# v12.net
KiCad netlist of a schematic drawn in Altium Designer
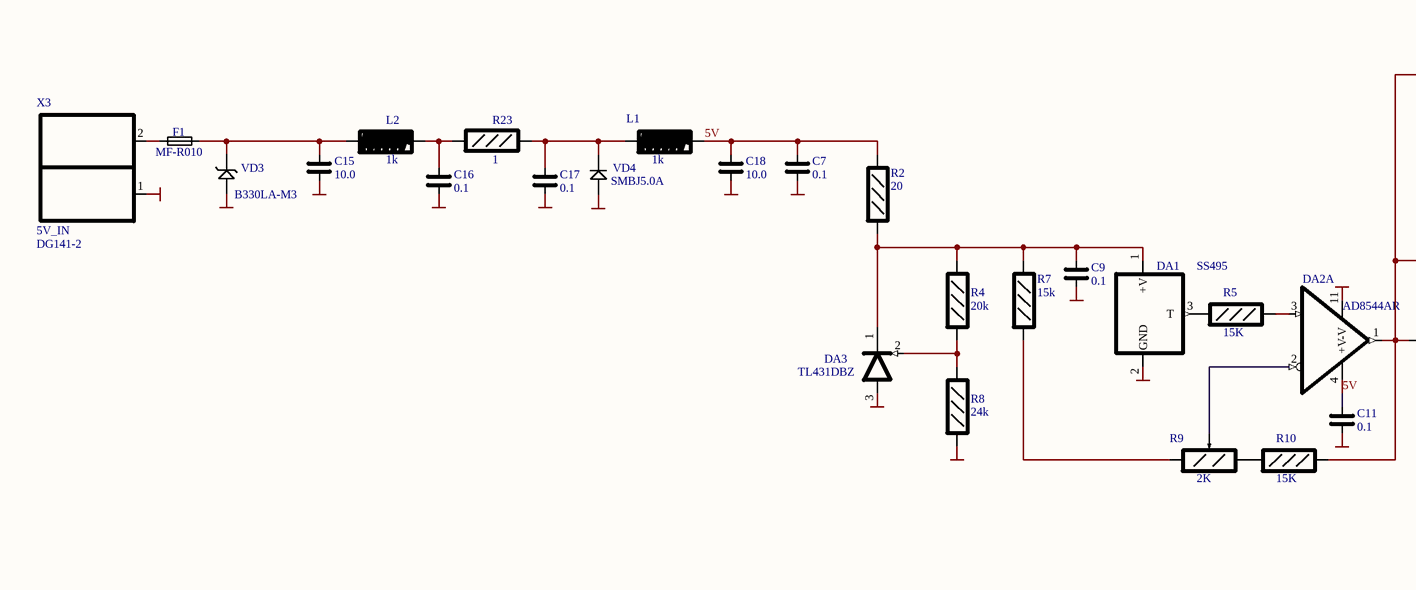
[diagram p0: v12.SchDoc, left]
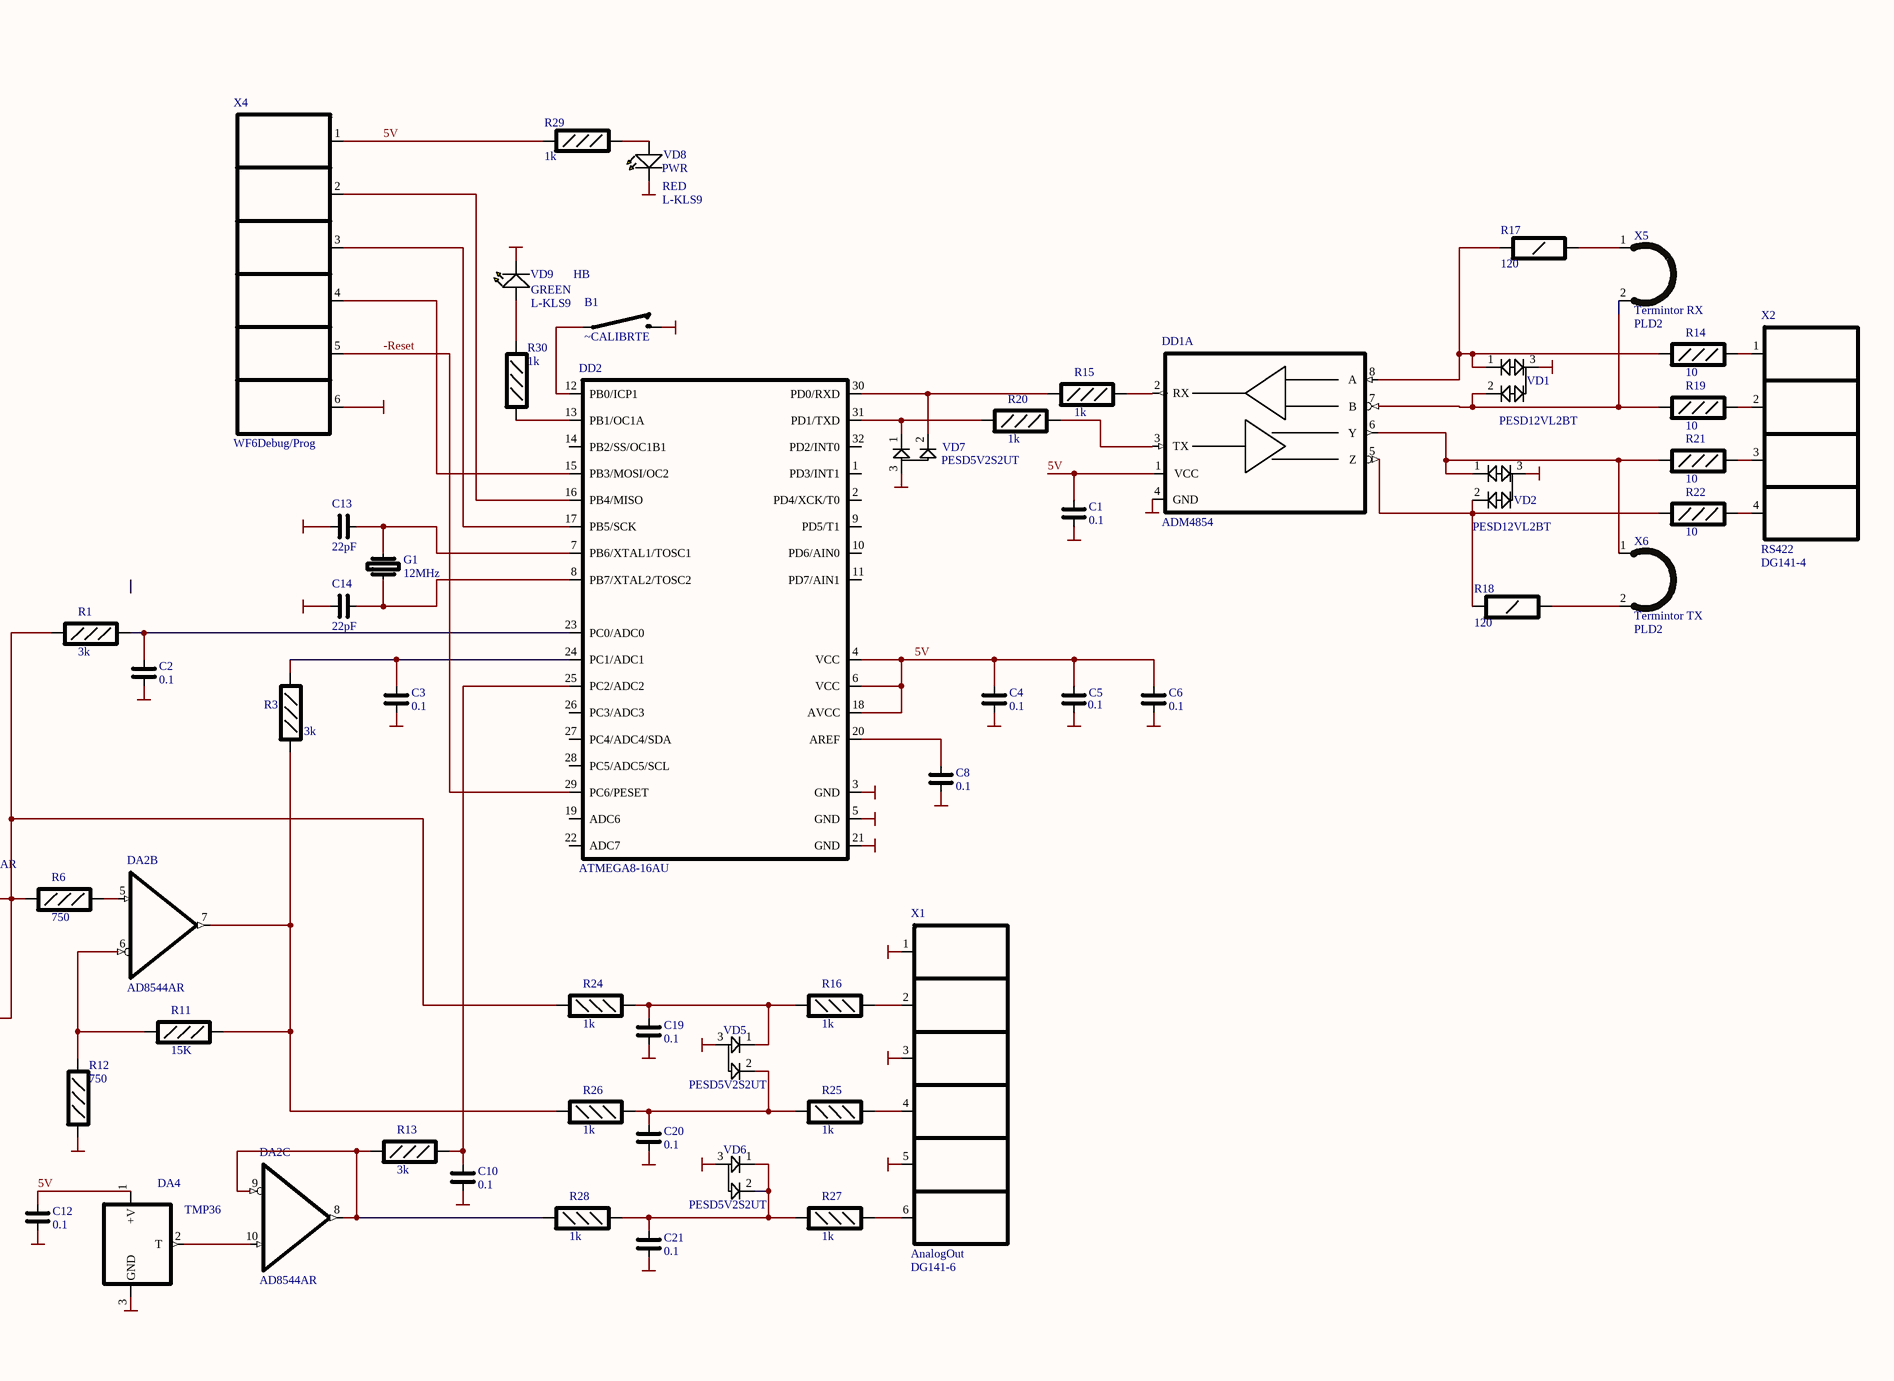
[diagram p1: v12.SchDoc, right]

(export (version "E")
  (design (tool "Eeschema 10.0.6"))
  (components
    (comp (ref "B1")
      (value "~CALIBRTE")
      (footprint "DIP_4-450_PB_OMRON_B3F-1070")
      (description "Push button wo latch")
      (libsource (lib "L1") (part "PushBt"))
    )
    (comp (ref "C1")
      (value "0.1")
      (footprint "CAPC1608X85N")
      (description "Chip capasitor 0603")
      (libsource (lib "L1") (part "CAP00603"))
    )
    (comp (ref "C2")
      (value "0.1")
      (footprint "CAPC1608X85N")
      (description "Chip capasitor 0603")
      (libsource (lib "L1") (part "CAP00603"))
    )
    (comp (ref "C3")
      (value "0.1")
      (footprint "CAPC1608X85N")
      (description "Chip capasitor 0603")
      (libsource (lib "L1") (part "CAP00603"))
    )
    (comp (ref "C4")
      (value "0.1")
      (footprint "CAPC1608X85N")
      (description "Chip capasitor 0603")
      (libsource (lib "L1") (part "CAP00603"))
    )
    (comp (ref "C5")
      (value "0.1")
      (footprint "CAPC1608X85N")
      (description "Chip capasitor 0603")
      (libsource (lib "L1") (part "CAP00603"))
    )
    (comp (ref "C6")
      (value "0.1")
      (footprint "CAPC1608X85N")
      (description "Chip capasitor 0603")
      (libsource (lib "L1") (part "CAP00603"))
    )
    (comp (ref "C7")
      (value "0.1")
      (footprint "CAPC1608X85N")
      (description "Chip capasitor 0603")
      (libsource (lib "L1") (part "CAP00603"))
    )
    (comp (ref "C8")
      (value "0.1")
      (footprint "CAPC1608X85N")
      (description "Chip capasitor 0603")
      (libsource (lib "L1") (part "CAP00603"))
    )
    (comp (ref "C9")
      (value "0.1")
      (footprint "CAPC1608X85N")
      (description "Chip capasitor 0603")
      (libsource (lib "L1") (part "CAP00603"))
    )
    (comp (ref "C10")
      (value "0.1")
      (footprint "CAPC1608X85N")
      (description "Chip capasitor 0603")
      (libsource (lib "L1") (part "CAP00603"))
    )
    (comp (ref "C11")
      (value "0.1")
      (footprint "CAPC1608X85N")
      (description "Chip capasitor 0603")
      (libsource (lib "L1") (part "CAP00603"))
    )
    (comp (ref "C12")
      (value "0.1")
      (footprint "CAPC1608X85N")
      (description "Chip capasitor 0603")
      (libsource (lib "L1") (part "CAP00603"))
    )
    (comp (ref "C13")
      (value "22pF")
      (footprint "CAPC1608X85N")
      (description "Chip capasitor 0603")
      (libsource (lib "L1") (part "CAP00603"))
    )
    (comp (ref "C14")
      (value "22pF")
      (footprint "CAPC1608X85N")
      (description "Chip capasitor 0603")
      (libsource (lib "L1") (part "CAP00603"))
    )
    (comp (ref "C15")
      (value "10.0")
      (footprint "CAPC3216X152N")
      (description "Chip capasitor 1206")
      (libsource (lib "L1") (part "CAP1206"))
    )
    (comp (ref "C16")
      (value "0.1")
      (footprint "CAPC1608X85N")
      (description "Chip capasitor 0603")
      (libsource (lib "L1") (part "CAP00603"))
    )
    (comp (ref "C17")
      (value "0.1")
      (footprint "CAPC1608X85N")
      (description "Chip capasitor 0603")
      (libsource (lib "L1") (part "CAP00603"))
    )
    (comp (ref "C18")
      (value "10.0")
      (footprint "CAPC3216X152N")
      (description "Chip capasitor 1206")
      (libsource (lib "L1") (part "CAP1206"))
    )
    (comp (ref "C19")
      (value "0.1")
      (footprint "CAPC1608X85N")
      (description "Chip capasitor 0603")
      (libsource (lib "L1") (part "CAP00603"))
    )
    (comp (ref "C20")
      (value "0.1")
      (footprint "CAPC1608X85N")
      (description "Chip capasitor 0603")
      (libsource (lib "L1") (part "CAP00603"))
    )
    (comp (ref "C21")
      (value "0.1")
      (footprint "CAPC1608X85N")
      (description "Chip capasitor 0603")
      (libsource (lib "L1") (part "CAP00603"))
    )
    (comp (ref "DA1")
      (value "SS495")
      (footprint "TO92H_3-127L - spec1")
      (description "10mV / C Temperature sensor")
      (libsource (lib "L1") (part "SS495"))
    )
    (comp (ref "DA2")
      (value "AD8544AR")
      (footprint "SOIC_14-127")
      (description "Quad rail to rail i&O OpAmp. 2V7-5V 5 Single power supply. MOSFET in. SOIC14 Package")
      (libsource (lib "L1") (part "AD8544AR"))
    )
    (comp (ref "DA3")
      (value "TL431DBZ")
      (footprint "SOT23-95")
      (description "Adjustable voltage reference")
      (libsource (lib "L1") (part "TL431DBZ"))
    )
    (comp (ref "DA4")
      (value "TMP36")
      (footprint "TO-92AA-P127")
      (description "10mV / C Temperature sensor")
      (libsource (lib "L1") (part "TMP36v"))
    )
    (comp (ref "DD1")
      (value "ADM4854")
      (footprint "SOIC8")
      (description "Full Duplex RS-422 Transceivers")
      (libsource (lib "L1") (part "ADM4854"))
    )
    (comp (ref "DD2")
      (value "ATMEGA8-16AU")
      (footprint "TQFP_32-80")
      (description "8bit uController")
      (libsource (lib "L1") (part "ATMEGA8-16AU"))
    )
    (comp (ref "F1")
      (value "MF-R010")
      (footprint "MF-R-508")
      (description "Fuse")
      (libsource (lib "L1") (part "MF-R-0"))
    )
    (comp (ref "G1")
      (value "12MHz")
      (footprint "XTAL_HC-49/U")
      (description "Quartz resonator")
      (libsource (lib "L1") (part "HC49U"))
    )
    (comp (ref "L1")
      (value "1k")
      (footprint "RESC2012X50N")
      (description "SMD Ferrite bead 0805")
      (libsource (lib "L1") (part "BLM21"))
    )
    (comp (ref "L2")
      (value "1k")
      (footprint "RESC2012X50N")
      (description "SMD Ferrite bead 0805")
      (libsource (lib "L1") (part "BLM21"))
    )
    (comp (ref "R1")
      (value "3k")
      (footprint "RESC1608X50N")
      (description "Chip resistor 0603")
      (libsource (lib "") (part "Res0603_2"))
    )
    (comp (ref "R2")
      (value "20")
      (footprint "RESC1608X50N")
      (description "Chip resistor 0603")
      (libsource (lib "") (part "Res0603_1"))
    )
    (comp (ref "R3")
      (value "3k")
      (footprint "RESC1608X50N")
      (description "Chip resistor 0603")
      (libsource (lib "") (part "Res0603_1"))
    )
    (comp (ref "R4")
      (value "20k")
      (footprint "RESC1608X50N")
      (description "Chip resistor 0603")
      (libsource (lib "") (part "Res0603_1"))
    )
    (comp (ref "R5")
      (value "15K")
      (footprint "RESC1608X50N")
      (description "Chip resistor 0603")
      (libsource (lib "") (part "Res0603_2"))
    )
    (comp (ref "R6")
      (value "750")
      (footprint "RESC1608X50N")
      (description "Chip resistor 0603")
      (libsource (lib "") (part "Res0603_2"))
    )
    (comp (ref "R7")
      (value "15k")
      (footprint "RESC1608X50N")
      (description "Chip resistor 0603")
      (libsource (lib "") (part "Res0603_1"))
    )
    (comp (ref "R8")
      (value "24k")
      (footprint "RESC1608X50N")
      (description "Chip resistor 0603")
      (libsource (lib "") (part "Res0603_1"))
    )
    (comp (ref "R9")
      (value "2K")
      (footprint "TRIM_BOURNS_3296Y")
      (description "Trimm Resistor")
      (libsource (lib "L1") (part "3296"))
    )
    (comp (ref "R10")
      (value "15K")
      (footprint "RESC1608X50N")
      (description "Chip resistor 0603")
      (libsource (lib "") (part "Res0603_2"))
    )
    (comp (ref "R11")
      (value "15K")
      (footprint "RESC1608X50N")
      (description "Chip resistor 0603")
      (libsource (lib "") (part "Res0603_2"))
    )
    (comp (ref "R12")
      (value "750")
      (footprint "RESC1608X50N")
      (description "Chip resistor 0603")
      (libsource (lib "") (part "Res0603_1"))
    )
    (comp (ref "R13")
      (value "3k")
      (footprint "RESC1608X50N")
      (description "Chip resistor 0603")
      (libsource (lib "") (part "Res0603_2"))
    )
    (comp (ref "R14")
      (value "10")
      (footprint "RESC1608X50N")
      (description "Chip resistor 0603")
      (libsource (lib "") (part "Res0603_2"))
    )
    (comp (ref "R15")
      (value "1k")
      (footprint "RESC1608X50N")
      (description "Chip resistor 0603")
      (libsource (lib "") (part "Res0603_2"))
    )
    (comp (ref "R16")
      (value "1k")
      (footprint "RESC1608X50N")
      (description "Chip resistor 0603")
      (libsource (lib "L1") (part "Res0603"))
    )
    (comp (ref "R17")
      (value "120")
      (footprint "RESC3216X65N")
      (description "Chip resistor 1206")
      (libsource (lib "L1") (part "Res1206"))
    )
    (comp (ref "R18")
      (value "120")
      (footprint "RESC3216X65N")
      (description "Chip resistor 1206")
      (libsource (lib "L1") (part "Res1206"))
    )
    (comp (ref "R19")
      (value "10")
      (footprint "RESC1608X50N")
      (description "Chip resistor 0603")
      (libsource (lib "") (part "Res0603_2"))
    )
    (comp (ref "R20")
      (value "1k")
      (footprint "RESC1608X50N")
      (description "Chip resistor 0603")
      (libsource (lib "") (part "Res0603_2"))
    )
    (comp (ref "R21")
      (value "10")
      (footprint "RESC1608X50N")
      (description "Chip resistor 0603")
      (libsource (lib "") (part "Res0603_2"))
    )
    (comp (ref "R22")
      (value "10")
      (footprint "RESC1608X50N")
      (description "Chip resistor 0603")
      (libsource (lib "") (part "Res0603_2"))
    )
    (comp (ref "R23")
      (value "1")
      (footprint "RESC1608X50N")
      (description "Chip resistor 0603")
      (libsource (lib "") (part "Res0603_3"))
    )
    (comp (ref "R24")
      (value "1k")
      (footprint "RESC1608X50N")
      (description "Chip resistor 0603")
      (libsource (lib "L1") (part "Res0603"))
    )
    (comp (ref "R25")
      (value "1k")
      (footprint "RESC1608X50N")
      (description "Chip resistor 0603")
      (libsource (lib "L1") (part "Res0603"))
    )
    (comp (ref "R26")
      (value "1k")
      (footprint "RESC1608X50N")
      (description "Chip resistor 0603")
      (libsource (lib "L1") (part "Res0603"))
    )
    (comp (ref "R27")
      (value "1k")
      (footprint "RESC1608X50N")
      (description "Chip resistor 0603")
      (libsource (lib "L1") (part "Res0603"))
    )
    (comp (ref "R28")
      (value "1k")
      (footprint "RESC1608X50N")
      (description "Chip resistor 0603")
      (libsource (lib "L1") (part "Res0603"))
    )
    (comp (ref "R29")
      (value "1k")
      (footprint "RESC1608X50N")
      (description "Chip resistor 0603")
      (libsource (lib "") (part "Res0603_3"))
    )
    (comp (ref "R30")
      (value "1k")
      (footprint "RESC1608X50N")
      (description "Chip resistor 0603")
      (libsource (lib "") (part "Res0603_1"))
    )
    (comp (ref "VD1")
      (value "PESD12VL2BT")
      (footprint "SO23-95")
      (description "Low capacitance double bidirectional ESD protection diodes in SOT23")
      (libsource (lib "L1") (part "PESDxxL2BT"))
    )
    (comp (ref "VD2")
      (value "PESD12VL2BT")
      (footprint "SO23-95")
      (description "Low capacitance double bidirectional ESD protection diodes in SOT23")
      (libsource (lib "L1") (part "PESDxxL2BT"))
    )
    (comp (ref "VD3")
      (value "B330LA-M3")
      (footprint "DO214")
      (description "3A 40V Schottky Diode")
      (libsource (lib "L1") (part "B330LA-M3"))
    )
    (comp (ref "VD4")
      (value "SMBJ5.0A")
      (footprint "DO214")
      (description "TVS surface mount diode")
      (libsource (lib "L1") (part "SMBJxxA"))
    )
    (comp (ref "VD5")
      (value "PESD5V2S2UT")
      (footprint "SO23-95")
      (description "Low capacitance double  ESD protection diodes in SOT23")
      (libsource (lib "L1") (part "PESDxxS2UT"))
    )
    (comp (ref "VD6")
      (value "PESD5V2S2UT")
      (footprint "SO23-95")
      (description "Low capacitance double  ESD protection diodes in SOT23")
      (libsource (lib "L1") (part "PESDxxS2UT"))
    )
    (comp (ref "VD7")
      (value "PESD5V2S2UT")
      (footprint "SO23-95")
      (description "Low capacitance double  ESD protection diodes in SOT23")
      (libsource (lib "L1") (part "PESDxxS2UT"))
    )
    (comp (ref "VD8")
      (value "PWR")
      (footprint "LED0603")
      (description "Chip LED SMD 0603")
      (fields (field (name "COLOR") "RED") (field (name "DEVICE") "L-KLS9"))
      (libsource (lib "L1") (part "L-KLS9-T0603"))
    )
    (comp (ref "VD9")
      (value "HB")
      (footprint "LED0603")
      (description "Chip LED SMD 0603")
      (fields (field (name "COLOR") "GREEN") (field (name "DEVICE") "L-KLS9"))
      (libsource (lib "L1") (part "L-KLS9-T0603"))
    )
    (comp (ref "X1")
      (value "AnalogOut")
      (footprint "DIP_CLEMM_6-254_F")
      (description "6 pin terminal spring clamp 2.54mm pitch")
      (fields (field (name "DEVICE") "DG141-6"))
      (libsource (lib "L1") (part "DG141-6"))
    )
    (comp (ref "X2")
      (value "RS422")
      (footprint "DIP_CLEMM_4-254_F")
      (description "4 pin terminal spring clamp 2.54mm pitch")
      (fields (field (name "DEVICE") "DG141-4"))
      (libsource (lib "L1") (part "DG141-4"))
    )
    (comp (ref "X3")
      (value "5V_IN")
      (footprint "DIP_CLEMM_2-254_F")
      (description "2 pin terminal spring clamp 2.54mm pitch")
      (fields (field (name "DEVICE") "DG141-2"))
      (libsource (lib "L1") (part "DG141-2"))
    )
    (comp (ref "X4")
      (value "WF6Debug/Prog")
      (footprint "SIP_6-254")
      (description "6 pin TRH connector 2.54mm pitch")
      (libsource (lib "L1") (part "WF6"))
    )
    (comp (ref "X5")
      (value "Termintor RX")
      (footprint "DIP_2-254_WO_CASE")
      (description "2 pin TRH connector 2.54mm pitch")
      (fields (field (name "DEVICE") "PLD2"))
      (libsource (lib "L1") (part "PLD2"))
    )
    (comp (ref "X6")
      (value "Termintor TX")
      (footprint "DIP_2-254_WO_CASE")
      (description "2 pin TRH connector 2.54mm pitch")
      (fields (field (name "DEVICE") "PLD2"))
      (libsource (lib "L1") (part "PLD2"))
    )
  )
  (nets
    (net (code "1") (name "/-Reset") (class "Default")
      (node (ref "DD2") (pin "29") (pinfunction "PC6/PESET_29") (pintype "passive"))
      (node (ref "X4") (pin "5") (pinfunction "5_5") (pintype "passive"))
    )
    (net (code "2") (name "/5V") (class "Default")
      (node (ref "C1") (pin "2") (pinfunction "2_2") (pintype "passive"))
      (node (ref "C11") (pin "2") (pinfunction "2_2") (pintype "passive"))
      (node (ref "C12") (pin "2") (pinfunction "2_2") (pintype "passive"))
      (node (ref "C18") (pin "2") (pinfunction "2_2") (pintype "passive"))
      (node (ref "C4") (pin "2") (pinfunction "2_2") (pintype "passive"))
      (node (ref "C5") (pin "2") (pinfunction "2_2") (pintype "passive"))
      (node (ref "C6") (pin "2") (pinfunction "2_2") (pintype "passive"))
      (node (ref "C7") (pin "2") (pinfunction "2_2") (pintype "passive"))
      (node (ref "DA2") (pin "4") (pinfunction "+V_4") (pintype "power_in"))
      (node (ref "DA4") (pin "1") (pinfunction "+V_1") (pintype "power_in"))
      (node (ref "DD1") (pin "1") (pinfunction "VCC_1") (pintype "power_in"))
      (node (ref "DD2") (pin "18") (pinfunction "AVCC_18") (pintype "passive"))
      (node (ref "DD2") (pin "4") (pinfunction "VCC_4") (pintype "passive"))
      (node (ref "DD2") (pin "6") (pinfunction "VCC_6") (pintype "passive"))
      (node (ref "L1") (pin "2") (pinfunction "2_2") (pintype "passive"))
      (node (ref "R2") (pin "2") (pinfunction "2_2") (pintype "passive"))
      (node (ref "R29") (pin "2") (pinfunction "2_2") (pintype "passive"))
      (node (ref "X4") (pin "1") (pinfunction "1_1") (pintype "passive"))
    )
    (net (code "3") (name "GND") (class "Default")
      (node (ref "B1") (pin "2") (pinfunction "2_2") (pintype "passive"))
      (node (ref "C1") (pin "1") (pinfunction "1_1") (pintype "passive"))
      (node (ref "C10") (pin "1") (pinfunction "1_1") (pintype "passive"))
      (node (ref "C11") (pin "1") (pinfunction "1_1") (pintype "passive"))
      (node (ref "C12") (pin "1") (pinfunction "1_1") (pintype "passive"))
      (node (ref "C13") (pin "1") (pinfunction "1_1") (pintype "passive"))
      (node (ref "C14") (pin "1") (pinfunction "1_1") (pintype "passive"))
      (node (ref "C15") (pin "1") (pinfunction "1_1") (pintype "passive"))
      (node (ref "C16") (pin "1") (pinfunction "1_1") (pintype "passive"))
      (node (ref "C17") (pin "1") (pinfunction "1_1") (pintype "passive"))
      (node (ref "C18") (pin "1") (pinfunction "1_1") (pintype "passive"))
      (node (ref "C19") (pin "1") (pinfunction "1_1") (pintype "passive"))
      (node (ref "C2") (pin "1") (pinfunction "1_1") (pintype "passive"))
      (node (ref "C20") (pin "1") (pinfunction "1_1") (pintype "passive"))
      (node (ref "C21") (pin "1") (pinfunction "1_1") (pintype "passive"))
      (node (ref "C3") (pin "1") (pinfunction "1_1") (pintype "passive"))
      (node (ref "C4") (pin "1") (pinfunction "1_1") (pintype "passive"))
      (node (ref "C5") (pin "1") (pinfunction "1_1") (pintype "passive"))
      (node (ref "C6") (pin "1") (pinfunction "1_1") (pintype "passive"))
      (node (ref "C7") (pin "1") (pinfunction "1_1") (pintype "passive"))
      (node (ref "C8") (pin "1") (pinfunction "1_1") (pintype "passive"))
      (node (ref "C9") (pin "1") (pinfunction "1_1") (pintype "passive"))
      (node (ref "DA1") (pin "2") (pinfunction "GND_2") (pintype "power_in"))
      (node (ref "DA2") (pin "11") (pinfunction "-V_11") (pintype "power_in"))
      (node (ref "DA3") (pin "3") (pinfunction "A_3") (pintype "passive"))
      (node (ref "DA4") (pin "3") (pinfunction "GND_3") (pintype "power_in"))
      (node (ref "DD1") (pin "4") (pinfunction "GND_4") (pintype "power_in"))
      (node (ref "DD2") (pin "21") (pinfunction "GND_21") (pintype "passive"))
      (node (ref "DD2") (pin "3") (pinfunction "GND_3") (pintype "passive"))
      (node (ref "DD2") (pin "5") (pinfunction "GND_5") (pintype "passive"))
      (node (ref "R12") (pin "1") (pinfunction "1_1") (pintype "passive"))
      (node (ref "R8") (pin "1") (pinfunction "1_1") (pintype "passive"))
      (node (ref "VD1") (pin "3") (pinfunction "CAT_COM_3") (pintype "passive"))
      (node (ref "VD2") (pin "3") (pinfunction "CAT_COM_3") (pintype "passive"))
      (node (ref "VD3") (pin "2") (pinfunction "A_2") (pintype "passive"))
      (node (ref "VD4") (pin "2") (pinfunction "A_2") (pintype "passive"))
      (node (ref "VD5") (pin "3") (pinfunction "CAT_COM_3") (pintype "passive"))
      (node (ref "VD6") (pin "3") (pinfunction "CAT_COM_3") (pintype "passive"))
      (node (ref "VD7") (pin "3") (pinfunction "CAT_COM_3") (pintype "passive"))
      (node (ref "VD8") (pin "1") (pinfunction "C_1") (pintype "passive"))
      (node (ref "VD9") (pin "1") (pinfunction "C_1") (pintype "passive"))
      (node (ref "X1") (pin "1") (pinfunction "1_1") (pintype "passive"))
      (node (ref "X1") (pin "3") (pinfunction "3_3") (pintype "passive"))
      (node (ref "X1") (pin "5") (pinfunction "5_5") (pintype "passive"))
      (node (ref "X3") (pin "1") (pinfunction "1_1") (pintype "passive"))
      (node (ref "X4") (pin "6") (pinfunction "6_6") (pintype "passive"))
    )
    (net (code "4") (name "Net-(C16-Pad2)") (class "Default")
      (node (ref "C16") (pin "2") (pinfunction "2_2") (pintype "passive"))
      (node (ref "L2") (pin "2") (pinfunction "2_2") (pintype "passive"))
      (node (ref "R23") (pin "2") (pinfunction "2_2") (pintype "passive"))
    )
    (net (code "5") (name "Net-(DA1-+V)") (class "Default")
      (node (ref "C9") (pin "2") (pinfunction "2_2") (pintype "passive"))
      (node (ref "DA1") (pin "1") (pinfunction "+V_1") (pintype "power_in"))
      (node (ref "DA3") (pin "1") (pinfunction "C_1") (pintype "passive"))
      (node (ref "R2") (pin "1") (pinfunction "1_1") (pintype "passive"))
      (node (ref "R4") (pin "2") (pinfunction "2_2") (pintype "passive"))
      (node (ref "R7") (pin "2") (pinfunction "2_2") (pintype "passive"))
    )
    (net (code "6") (name "Net-(DA1-T)") (class "Default")
      (node (ref "DA1") (pin "3") (pinfunction "T_3") (pintype "output"))
      (node (ref "R5") (pin "1") (pinfunction "1_1") (pintype "passive"))
    )
    (net (code "7") (name "Net-(DA2A-+IN)") (class "Default")
      (node (ref "DA2") (pin "3") (pinfunction "+IN_3") (pintype "input"))
      (node (ref "R5") (pin "2") (pinfunction "2_2") (pintype "passive"))
    )
    (net (code "8") (name "Net-(DA2A--IN)") (class "Default")
      (node (ref "DA2") (pin "2") (pinfunction "-IN_2") (pintype "input"))
      (node (ref "R9") (pin "3") (pinfunction "3_3") (pintype "passive"))
    )
    (net (code "9") (name "Net-(DA2A-OUT)") (class "Default")
      (node (ref "DA2") (pin "1") (pinfunction "OUT_1") (pintype "output"))
      (node (ref "R1") (pin "1") (pinfunction "1_1") (pintype "passive"))
      (node (ref "R10") (pin "2") (pinfunction "2_2") (pintype "passive"))
      (node (ref "R24") (pin "2") (pinfunction "2_2") (pintype "passive"))
      (node (ref "R6") (pin "1") (pinfunction "1_1") (pintype "passive"))
    )
    (net (code "10") (name "Net-(DA2B-+IN)") (class "Default")
      (node (ref "DA2") (pin "5") (pinfunction "+IN_5") (pintype "input"))
      (node (ref "R6") (pin "2") (pinfunction "2_2") (pintype "passive"))
    )
    (net (code "11") (name "Net-(DA2B--IN)") (class "Default")
      (node (ref "DA2") (pin "6") (pinfunction "-IN_6") (pintype "input"))
      (node (ref "R11") (pin "1") (pinfunction "1_1") (pintype "passive"))
      (node (ref "R12") (pin "2") (pinfunction "2_2") (pintype "passive"))
    )
    (net (code "12") (name "Net-(DA2B-OUT)") (class "Default")
      (node (ref "DA2") (pin "7") (pinfunction "OUT_7") (pintype "output"))
      (node (ref "R11") (pin "2") (pinfunction "2_2") (pintype "passive"))
      (node (ref "R26") (pin "2") (pinfunction "2_2") (pintype "passive"))
      (node (ref "R3") (pin "1") (pinfunction "1_1") (pintype "passive"))
    )
    (net (code "13") (name "Net-(DA2C-+IN)") (class "Default")
      (node (ref "DA2") (pin "10") (pinfunction "+IN_10") (pintype "input"))
      (node (ref "DA4") (pin "2") (pinfunction "T_2") (pintype "output"))
    )
    (net (code "14") (name "Net-(DA2C--IN)") (class "Default")
      (node (ref "DA2") (pin "8") (pinfunction "OUT_8") (pintype "output"))
      (node (ref "DA2") (pin "9") (pinfunction "-IN_9") (pintype "input"))
      (node (ref "R13") (pin "1") (pinfunction "1_1") (pintype "passive"))
      (node (ref "R28") (pin "2") (pinfunction "2_2") (pintype "passive"))
    )
    (net (code "15") (name "Net-(DA3-Ref)") (class "Default")
      (node (ref "DA3") (pin "2") (pinfunction "Ref_2") (pintype "input"))
      (node (ref "R4") (pin "1") (pinfunction "1_1") (pintype "passive"))
      (node (ref "R8") (pin "2") (pinfunction "2_2") (pintype "passive"))
    )
    (net (code "16") (name "Net-(DD1-A)") (class "Default")
      (node (ref "DD1") (pin "8") (pinfunction "A_8") (pintype "input"))
      (node (ref "R14") (pin "1") (pinfunction "1_1") (pintype "passive"))
      (node (ref "R17") (pin "1") (pinfunction "1_1") (pintype "passive"))
      (node (ref "VD1") (pin "1") (pinfunction "C1_1") (pintype "passive"))
    )
    (net (code "17") (name "Net-(DD1-B)") (class "Default")
      (node (ref "DD1") (pin "7") (pinfunction "B_7") (pintype "input"))
      (node (ref "R19") (pin "1") (pinfunction "1_1") (pintype "passive"))
      (node (ref "VD1") (pin "2") (pinfunction "C2_2") (pintype "passive"))
      (node (ref "X5") (pin "2") (pinfunction "2_2") (pintype "passive"))
    )
    (net (code "18") (name "Net-(DD1-RX)") (class "Default")
      (node (ref "DD1") (pin "2") (pinfunction "RX_2") (pintype "output"))
      (node (ref "R15") (pin "2") (pinfunction "2_2") (pintype "passive"))
    )
    (net (code "19") (name "Net-(DD1-TX)") (class "Default")
      (node (ref "DD1") (pin "3") (pinfunction "TX_3") (pintype "input"))
      (node (ref "R20") (pin "2") (pinfunction "2_2") (pintype "passive"))
    )
    (net (code "20") (name "Net-(DD1-Y)") (class "Default")
      (node (ref "DD1") (pin "6") (pinfunction "Y_6") (pintype "output"))
      (node (ref "R21") (pin "1") (pinfunction "1_1") (pintype "passive"))
      (node (ref "VD2") (pin "1") (pinfunction "C1_1") (pintype "passive"))
      (node (ref "X6") (pin "1") (pinfunction "1_1") (pintype "passive"))
    )
    (net (code "21") (name "Net-(DD1-Z)") (class "Default")
      (node (ref "DD1") (pin "5") (pinfunction "Z_5") (pintype "output"))
      (node (ref "R18") (pin "1") (pinfunction "1_1") (pintype "passive"))
      (node (ref "R22") (pin "1") (pinfunction "1_1") (pintype "passive"))
      (node (ref "VD2") (pin "2") (pinfunction "C2_2") (pintype "passive"))
    )
    (net (code "22") (name "Net-(DD2-AREF)") (class "Default")
      (node (ref "C8") (pin "2") (pinfunction "2_2") (pintype "passive"))
      (node (ref "DD2") (pin "20") (pinfunction "AREF_20") (pintype "passive"))
    )
    (net (code "23") (name "Net-(DD2-PB0{slash}ICP1)") (class "Default")
      (node (ref "B1") (pin "1") (pinfunction "1_1") (pintype "passive"))
      (node (ref "DD2") (pin "12") (pinfunction "PB0/ICP1_12") (pintype "passive"))
    )
    (net (code "24") (name "Net-(DD2-PB1{slash}OC1A)") (class "Default")
      (node (ref "DD2") (pin "13") (pinfunction "PB1/OC1A_13") (pintype "passive"))
      (node (ref "R30") (pin "1") (pinfunction "1_1") (pintype "passive"))
    )
    (net (code "25") (name "Net-(DD2-PB3{slash}MOSI{slash}OC2)") (class "Default")
      (node (ref "DD2") (pin "15") (pinfunction "PB3/MOSI/OC2_15") (pintype "passive"))
      (node (ref "X4") (pin "4") (pinfunction "4_4") (pintype "passive"))
    )
    (net (code "26") (name "Net-(DD2-PB4{slash}MISO)") (class "Default")
      (node (ref "DD2") (pin "16") (pinfunction "PB4/MISO_16") (pintype "passive"))
      (node (ref "X4") (pin "2") (pinfunction "2_2") (pintype "passive"))
    )
    (net (code "27") (name "Net-(DD2-PB5{slash}SCK)") (class "Default")
      (node (ref "DD2") (pin "17") (pinfunction "PB5/SCK_17") (pintype "passive"))
      (node (ref "X4") (pin "3") (pinfunction "3_3") (pintype "passive"))
    )
    (net (code "28") (name "Net-(DD2-PB6{slash}XTAL1{slash}TOSC1)") (class "Default")
      (node (ref "C13") (pin "2") (pinfunction "2_2") (pintype "passive"))
      (node (ref "DD2") (pin "7") (pinfunction "PB6/XTAL1/TOSC1_7") (pintype "passive"))
      (node (ref "G1") (pin "2") (pinfunction "2_2") (pintype "passive"))
    )
    (net (code "29") (name "Net-(DD2-PB7{slash}XTAL2{slash}TOSC2)") (class "Default")
      (node (ref "C14") (pin "2") (pinfunction "2_2") (pintype "passive"))
      (node (ref "DD2") (pin "8") (pinfunction "PB7/XTAL2/TOSC2_8") (pintype "passive"))
      (node (ref "G1") (pin "1") (pinfunction "1_1") (pintype "passive"))
    )
    (net (code "30") (name "Net-(DD2-PC0{slash}ADC0)") (class "Default")
      (node (ref "C2") (pin "2") (pinfunction "2_2") (pintype "passive"))
      (node (ref "DD2") (pin "23") (pinfunction "PC0/ADC0_23") (pintype "passive"))
      (node (ref "R1") (pin "2") (pinfunction "2_2") (pintype "passive"))
    )
    (net (code "31") (name "Net-(DD2-PC1{slash}ADC1)") (class "Default")
      (node (ref "C3") (pin "2") (pinfunction "2_2") (pintype "passive"))
      (node (ref "DD2") (pin "24") (pinfunction "PC1/ADC1_24") (pintype "passive"))
      (node (ref "R3") (pin "2") (pinfunction "2_2") (pintype "passive"))
    )
    (net (code "32") (name "Net-(DD2-PC2{slash}ADC2)") (class "Default")
      (node (ref "C10") (pin "2") (pinfunction "2_2") (pintype "passive"))
      (node (ref "DD2") (pin "25") (pinfunction "PC2/ADC2_25") (pintype "passive"))
      (node (ref "R13") (pin "2") (pinfunction "2_2") (pintype "passive"))
    )
    (net (code "33") (name "Net-(DD2-PD0{slash}RXD)") (class "Default")
      (node (ref "DD2") (pin "30") (pinfunction "PD0/RXD_30") (pintype "passive"))
      (node (ref "R15") (pin "1") (pinfunction "1_1") (pintype "passive"))
      (node (ref "VD7") (pin "2") (pinfunction "C2_2") (pintype "passive"))
    )
    (net (code "34") (name "Net-(DD2-PD1{slash}TXD)") (class "Default")
      (node (ref "DD2") (pin "31") (pinfunction "PD1/TXD_31") (pintype "passive"))
      (node (ref "R20") (pin "1") (pinfunction "1_1") (pintype "passive"))
      (node (ref "VD7") (pin "1") (pinfunction "C1_1") (pintype "passive"))
    )
    (net (code "35") (name "Net-(F1-Pad1)") (class "Default")
      (node (ref "F1") (pin "1") (pinfunction "1_1") (pintype "passive"))
      (node (ref "X3") (pin "2") (pinfunction "2_2") (pintype "passive"))
    )
    (net (code "36") (name "Net-(R7-Pad1)") (class "Default")
      (node (ref "R7") (pin "1") (pinfunction "1_1") (pintype "passive"))
      (node (ref "R9") (pin "1") (pinfunction "1_1") (pintype "passive"))
    )
    (net (code "37") (name "Net-(R10-Pad1)") (class "Default")
      (node (ref "R10") (pin "1") (pinfunction "1_1") (pintype "passive"))
      (node (ref "R9") (pin "2") (pinfunction "2_2") (pintype "passive"))
    )
    (net (code "38") (name "Net-(R14-Pad2)") (class "Default")
      (node (ref "R14") (pin "2") (pinfunction "2_2") (pintype "passive"))
      (node (ref "X2") (pin "1") (pinfunction "1_1") (pintype "passive"))
    )
    (net (code "39") (name "Net-(R16-Pad1)") (class "Default")
      (node (ref "R16") (pin "1") (pinfunction "1_1") (pintype "passive"))
      (node (ref "X1") (pin "2") (pinfunction "2_2") (pintype "passive"))
    )
    (net (code "40") (name "Net-(R17-Pad2)") (class "Default")
      (node (ref "R17") (pin "2") (pinfunction "2_2") (pintype "passive"))
      (node (ref "X5") (pin "1") (pinfunction "1_1") (pintype "passive"))
    )
    (net (code "41") (name "Net-(R18-Pad2)") (class "Default")
      (node (ref "R18") (pin "2") (pinfunction "2_2") (pintype "passive"))
      (node (ref "X6") (pin "2") (pinfunction "2_2") (pintype "passive"))
    )
    (net (code "42") (name "Net-(R19-Pad2)") (class "Default")
      (node (ref "R19") (pin "2") (pinfunction "2_2") (pintype "passive"))
      (node (ref "X2") (pin "2") (pinfunction "2_2") (pintype "passive"))
    )
    (net (code "43") (name "Net-(R21-Pad2)") (class "Default")
      (node (ref "R21") (pin "2") (pinfunction "2_2") (pintype "passive"))
      (node (ref "X2") (pin "3") (pinfunction "3_3") (pintype "passive"))
    )
    (net (code "44") (name "Net-(R22-Pad2)") (class "Default")
      (node (ref "R22") (pin "2") (pinfunction "2_2") (pintype "passive"))
      (node (ref "X2") (pin "4") (pinfunction "4_4") (pintype "passive"))
    )
    (net (code "45") (name "Net-(R25-Pad1)") (class "Default")
      (node (ref "R25") (pin "1") (pinfunction "1_1") (pintype "passive"))
      (node (ref "X1") (pin "4") (pinfunction "4_4") (pintype "passive"))
    )
    (net (code "46") (name "Net-(R27-Pad1)") (class "Default")
      (node (ref "R27") (pin "1") (pinfunction "1_1") (pintype "passive"))
      (node (ref "X1") (pin "6") (pinfunction "6_6") (pintype "passive"))
    )
    (net (code "47") (name "Net-(VD3-C)") (class "Default")
      (node (ref "C15") (pin "2") (pinfunction "2_2") (pintype "passive"))
      (node (ref "F1") (pin "2") (pinfunction "2_2") (pintype "passive"))
      (node (ref "L2") (pin "1") (pinfunction "1_1") (pintype "passive"))
      (node (ref "VD3") (pin "1") (pinfunction "C_1") (pintype "passive"))
    )
    (net (code "48") (name "Net-(VD4-C)") (class "Default")
      (node (ref "C17") (pin "2") (pinfunction "2_2") (pintype "passive"))
      (node (ref "L1") (pin "1") (pinfunction "1_1") (pintype "passive"))
      (node (ref "R23") (pin "1") (pinfunction "1_1") (pintype "passive"))
      (node (ref "VD4") (pin "1") (pinfunction "C_1") (pintype "passive"))
    )
    (net (code "49") (name "Net-(VD5-C1)") (class "Default")
      (node (ref "C19") (pin "2") (pinfunction "2_2") (pintype "passive"))
      (node (ref "R16") (pin "2") (pinfunction "2_2") (pintype "passive"))
      (node (ref "R24") (pin "1") (pinfunction "1_1") (pintype "passive"))
      (node (ref "VD5") (pin "1") (pinfunction "C1_1") (pintype "passive"))
    )
    (net (code "50") (name "Net-(VD5-C2)") (class "Default")
      (node (ref "C20") (pin "2") (pinfunction "2_2") (pintype "passive"))
      (node (ref "R25") (pin "2") (pinfunction "2_2") (pintype "passive"))
      (node (ref "R26") (pin "1") (pinfunction "1_1") (pintype "passive"))
      (node (ref "VD5") (pin "2") (pinfunction "C2_2") (pintype "passive"))
    )
    (net (code "51") (name "Net-(VD6-C1)") (class "Default")
      (node (ref "C21") (pin "2") (pinfunction "2_2") (pintype "passive"))
      (node (ref "R27") (pin "2") (pinfunction "2_2") (pintype "passive"))
      (node (ref "R28") (pin "1") (pinfunction "1_1") (pintype "passive"))
      (node (ref "VD6") (pin "1") (pinfunction "C1_1") (pintype "passive"))
      (node (ref "VD6") (pin "2") (pinfunction "C2_2") (pintype "passive"))
    )
    (net (code "52") (name "Net-(VD8-A)") (class "Default")
      (node (ref "R29") (pin "1") (pinfunction "1_1") (pintype "passive"))
      (node (ref "VD8") (pin "2") (pinfunction "A_2") (pintype "passive"))
    )
    (net (code "53") (name "Net-(VD9-A)") (class "Default")
      (node (ref "R30") (pin "2") (pinfunction "2_2") (pintype "passive"))
      (node (ref "VD9") (pin "2") (pinfunction "A_2") (pintype "passive"))
    )
    (net (code "54") (name "unconnected-(DD2-ADC6-Pad19)") (class "Default")
      (node (ref "DD2") (pin "19") (pinfunction "ADC6_19") (pintype "passive"))
    )
    (net (code "55") (name "unconnected-(DD2-ADC7-Pad22)") (class "Default")
      (node (ref "DD2") (pin "22") (pinfunction "ADC7_22") (pintype "passive"))
    )
    (net (code "56") (name "unconnected-(DD2-PB2{slash}SS{slash}OC1B1-Pad14)") (class "Default")
      (node (ref "DD2") (pin "14") (pinfunction "PB2/SS/OC1B1_14") (pintype "passive"))
    )
    (net (code "57") (name "unconnected-(DD2-PC3{slash}ADC3-Pad26)") (class "Default")
      (node (ref "DD2") (pin "26") (pinfunction "PC3/ADC3_26") (pintype "passive"))
    )
    (net (code "58") (name "unconnected-(DD2-PC4{slash}ADC4{slash}SDA-Pad27)") (class "Default")
      (node (ref "DD2") (pin "27") (pinfunction "PC4/ADC4/SDA_27") (pintype "passive"))
    )
    (net (code "59") (name "unconnected-(DD2-PC5{slash}ADC5{slash}SCL-Pad28)") (class "Default")
      (node (ref "DD2") (pin "28") (pinfunction "PC5/ADC5/SCL_28") (pintype "passive"))
    )
    (net (code "60") (name "unconnected-(DD2-PD2{slash}INT0-Pad32)") (class "Default")
      (node (ref "DD2") (pin "32") (pinfunction "PD2/INT0_32") (pintype "passive"))
    )
    (net (code "61") (name "unconnected-(DD2-PD3{slash}INT1-Pad1)") (class "Default")
      (node (ref "DD2") (pin "1") (pinfunction "PD3/INT1_1") (pintype "passive"))
    )
    (net (code "62") (name "unconnected-(DD2-PD4{slash}XCK{slash}T0-Pad2)") (class "Default")
      (node (ref "DD2") (pin "2") (pinfunction "PD4/XCK/T0_2") (pintype "passive"))
    )
    (net (code "63") (name "unconnected-(DD2-PD5{slash}T1-Pad9)") (class "Default")
      (node (ref "DD2") (pin "9") (pinfunction "PD5/T1_9") (pintype "passive"))
    )
    (net (code "64") (name "unconnected-(DD2-PD6{slash}AIN0-Pad10)") (class "Default")
      (node (ref "DD2") (pin "10") (pinfunction "PD6/AIN0_10") (pintype "passive"))
    )
    (net (code "65") (name "unconnected-(DD2-PD7{slash}AIN1-Pad11)") (class "Default")
      (node (ref "DD2") (pin "11") (pinfunction "PD7/AIN1_11") (pintype "passive"))
    )
  )
)
